# STM32F030P4-DevBoard.net
KiCad netlist of a schematic drawn in Altium Designer
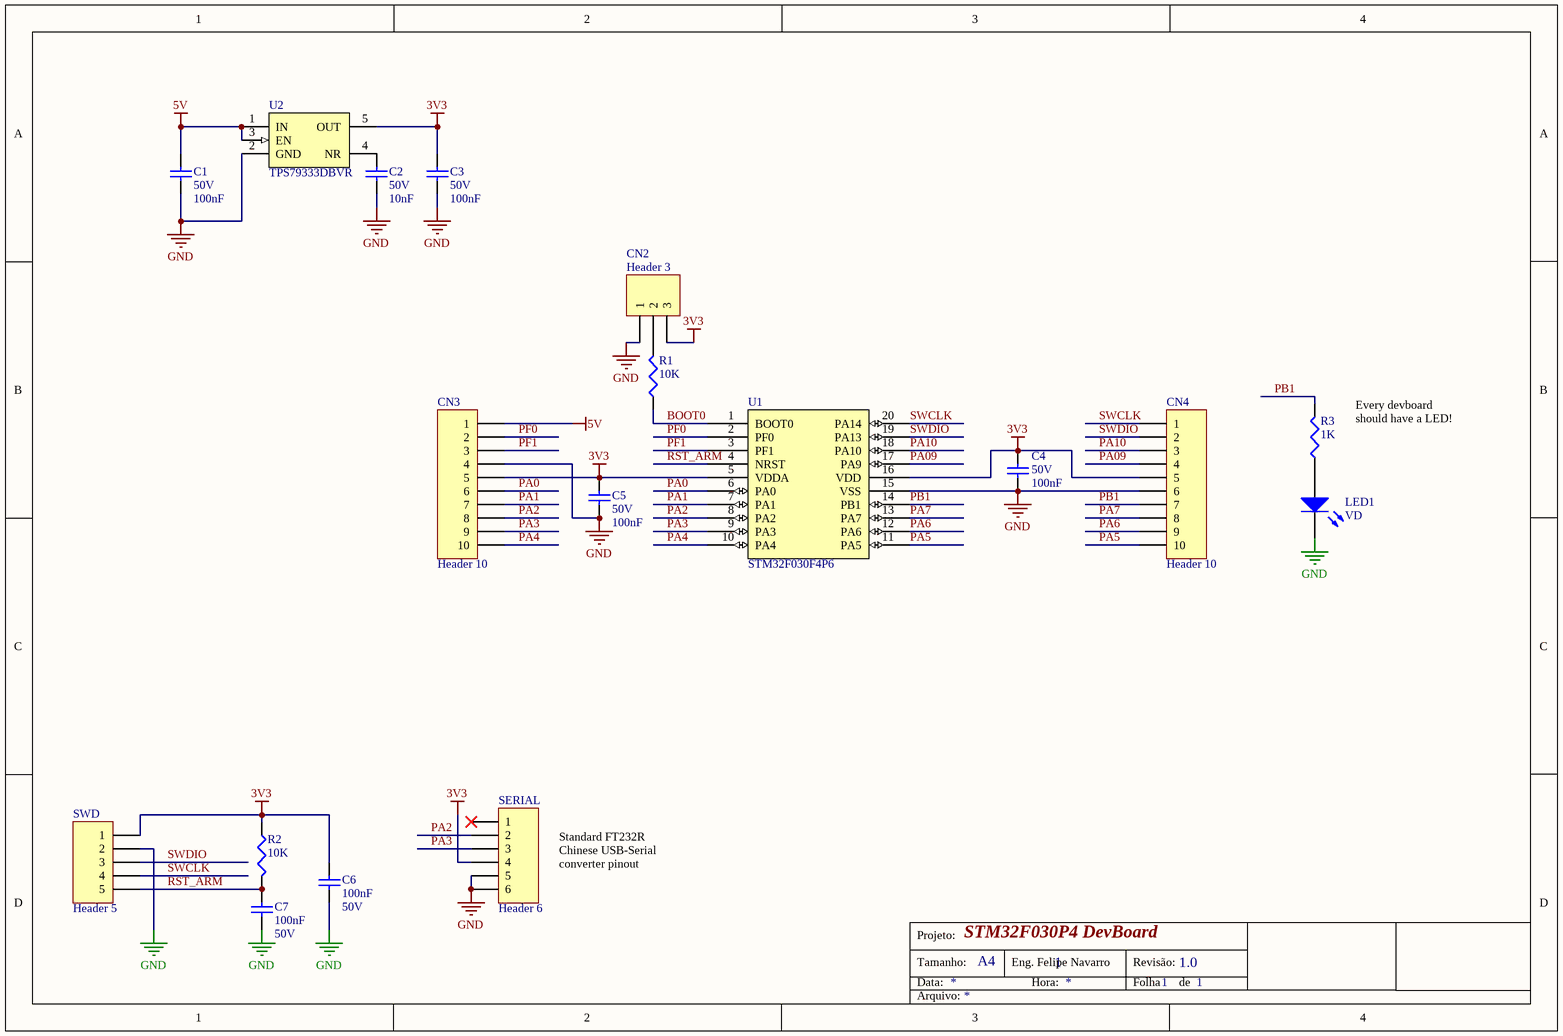
[diagram p0: STM32F030P4-DevBoard.SchDoc]

(export (version "E")
  (design (tool "Eeschema 10.0.6"))
  (components
    (comp (ref "C1")
      (value "100nF")
      (footprint "CC0603")
      (description "Capacitor (Semiconductor SIM Model)")
      (fields (field (name "TENSÃO") "50V") (field (name "Comment") "Capacitor Cerâmico"))
      (libsource (lib "NavarroCAP") (part "Cap 100nF 50V 0603 X7R"))
    )
    (comp (ref "C2")
      (value "10nF")
      (footprint "CC0603")
      (description "Capacitor (Semiconductor SIM Model)")
      (fields (field (name "TENSÃO") "50V") (field (name "Comment") "Capacitor Cerâmico"))
      (libsource (lib "NavarroCAP") (part "Cap 10nF 50V 0603 X7R 5%"))
    )
    (comp (ref "C3")
      (value "100nF")
      (footprint "CC0603")
      (description "Capacitor (Semiconductor SIM Model)")
      (fields (field (name "TENSÃO") "50V") (field (name "Comment") "Capacitor Cerâmico"))
      (libsource (lib "NavarroCAP") (part "Cap 100nF 50V 0603 X7R"))
    )
    (comp (ref "C4")
      (value "100nF")
      (footprint "CC0603")
      (description "Capacitor (Semiconductor SIM Model)")
      (fields (field (name "TENSÃO") "50V") (field (name "Comment") "Capacitor Cerâmico"))
      (libsource (lib "NavarroCAP") (part "Cap 100nF 50V 0603 X7R"))
    )
    (comp (ref "C5")
      (value "100nF")
      (footprint "CC0603")
      (description "Capacitor (Semiconductor SIM Model)")
      (fields (field (name "TENSÃO") "50V") (field (name "Comment") "Capacitor Cerâmico"))
      (libsource (lib "NavarroCAP") (part "Cap 100nF 50V 0603 X7R"))
    )
    (comp (ref "C6")
      (value "100nF")
      (footprint "CC0603")
      (description "Capacitor (Semiconductor SIM Model)")
      (fields (field (name "TENSÃO") "50V") (field (name "Comment") "Capacitor Cerâmico"))
      (libsource (lib "TecnocladeCAP") (part "Cap 100nF 50V 0603 X7R"))
    )
    (comp (ref "C7")
      (value "100nF")
      (footprint "CC0603")
      (description "Capacitor (Semiconductor SIM Model)")
      (fields (field (name "TENSÃO") "50V") (field (name "Comment") "Capacitor Cerâmico"))
      (libsource (lib "TecnocladeCAP") (part "Cap 100nF 50V 0603 X7R"))
    )
    (comp (ref "CN2")
      (value "Header 3")
      (footprint "CONN HDR1X3")
      (description "Header, 3-Pin")
      (libsource (lib "NavarroCON") (part "Header 3"))
    )
    (comp (ref "CN3")
      (value "Header 10")
      (footprint "CONN HDR1X10")
      (description "Header, 10-Pin")
      (libsource (lib "NavarroCON") (part "Header 10"))
    )
    (comp (ref "CN4")
      (value "Header 10")
      (footprint "CONN HDR1X10")
      (description "Header, 10-Pin")
      (libsource (lib "") (part "Header 10_1"))
    )
    (comp (ref "LED1")
      (value "VD")
      (footprint "LED 0603")
      (description "LED")
      (libsource (lib "NavarroSEMI") (part "LED 0603 VD 2V 75mW"))
    )
    (comp (ref "R1")
      (value "10K")
      (footprint "CC0603")
      (description "Resistor")
      (libsource (lib "NavarroRES") (part "Res 10K 1% 0603 1/10W"))
    )
    (comp (ref "R2")
      (value "10K")
      (footprint "CC0603")
      (description "Resistor")
      (libsource (lib "TecnocladeRES") (part "Res 10K 1% 0603 1/10W"))
    )
    (comp (ref "R3")
      (value "1K")
      (footprint "CC0603")
      (description "Resistor")
      (libsource (lib "NavarroRES") (part "Res 1K 1% 0603 1/10W"))
    )
    (comp (ref "SERIAL")
      (value "Header 6")
      (footprint "CONN HDR1X6")
      (description "Header, 6-Pin")
      (libsource (lib "NavarroCON") (part "Header 6"))
    )
    (comp (ref "SWD")
      (value "Header 5")
      (footprint "CONN HDR1X5")
      (description "Header, 5-Pin")
      (libsource (lib "TecnocladeCON") (part "Header 5"))
    )
    (comp (ref "U1")
      (value "STM32F030F4P6")
      (footprint "TSSOP-20N")
      (description "Microcontrolador STM32F030F4P6")
      (libsource (lib "Navarro") (part "STM32F030F4P6"))
    )
    (comp (ref "U2")
      (value "TPS79333DBVR")
      (footprint "SOT-23-5N")
      (description "ULTRALOW-NOISE, HIGH PSRR, FAST RF 200mA LOW-DROPOUT LINEAR  REGULATORS I")
      (libsource (lib "Navarro") (part "TPS79333"))
    )
  )
  (nets
    (net (code "1") (name "/BOOT0") (class "Default")
      (node (ref "R1") (pin "1") (pinfunction "1_1") (pintype "passive"))
      (node (ref "U1") (pin "1") (pinfunction "BOOT0_1") (pintype "passive"))
    )
    (net (code "2") (name "/PA0") (class "Default")
      (node (ref "CN3") (pin "6") (pinfunction "6_6") (pintype "passive"))
      (node (ref "U1") (pin "6") (pinfunction "PA0_6") (pintype "bidirectional"))
    )
    (net (code "3") (name "/PA1") (class "Default")
      (node (ref "CN3") (pin "7") (pinfunction "7_7") (pintype "passive"))
      (node (ref "U1") (pin "7") (pinfunction "PA1_7") (pintype "bidirectional"))
    )
    (net (code "4") (name "/PA2") (class "Default")
      (node (ref "CN3") (pin "8") (pinfunction "8_8") (pintype "passive"))
      (node (ref "SERIAL") (pin "2") (pinfunction "2_2") (pintype "passive"))
      (node (ref "U1") (pin "8") (pinfunction "PA2_8") (pintype "bidirectional"))
    )
    (net (code "5") (name "/PA3") (class "Default")
      (node (ref "CN3") (pin "9") (pinfunction "9_9") (pintype "passive"))
      (node (ref "SERIAL") (pin "3") (pinfunction "3_3") (pintype "passive"))
      (node (ref "U1") (pin "9") (pinfunction "PA3_9") (pintype "bidirectional"))
    )
    (net (code "6") (name "/PA4") (class "Default")
      (node (ref "CN3") (pin "10") (pinfunction "10_10") (pintype "passive"))
      (node (ref "U1") (pin "10") (pinfunction "PA4_10") (pintype "bidirectional"))
    )
    (net (code "7") (name "/PA5") (class "Default")
      (node (ref "CN4") (pin "10") (pinfunction "10_10") (pintype "passive"))
      (node (ref "U1") (pin "11") (pinfunction "PA5_11") (pintype "bidirectional"))
    )
    (net (code "8") (name "/PA6") (class "Default")
      (node (ref "CN4") (pin "9") (pinfunction "9_9") (pintype "passive"))
      (node (ref "U1") (pin "12") (pinfunction "PA6_12") (pintype "bidirectional"))
    )
    (net (code "9") (name "/PA7") (class "Default")
      (node (ref "CN4") (pin "8") (pinfunction "8_8") (pintype "passive"))
      (node (ref "U1") (pin "13") (pinfunction "PA7_13") (pintype "bidirectional"))
    )
    (net (code "10") (name "/PA09") (class "Default")
      (node (ref "CN4") (pin "4") (pinfunction "4_4") (pintype "passive"))
      (node (ref "U1") (pin "17") (pinfunction "PA9_17") (pintype "bidirectional"))
    )
    (net (code "11") (name "/PA10") (class "Default")
      (node (ref "CN4") (pin "3") (pinfunction "3_3") (pintype "passive"))
      (node (ref "U1") (pin "18") (pinfunction "PA10_18") (pintype "bidirectional"))
    )
    (net (code "12") (name "/PB1") (class "Default")
      (node (ref "CN4") (pin "7") (pinfunction "7_7") (pintype "passive"))
      (node (ref "R3") (pin "2") (pinfunction "2_2") (pintype "passive"))
      (node (ref "U1") (pin "14") (pinfunction "PB1_14") (pintype "bidirectional"))
    )
    (net (code "13") (name "/PF0") (class "Default")
      (node (ref "CN3") (pin "2") (pinfunction "2_2") (pintype "passive"))
      (node (ref "U1") (pin "2") (pinfunction "PF0_2") (pintype "passive"))
    )
    (net (code "14") (name "/PF1") (class "Default")
      (node (ref "CN3") (pin "3") (pinfunction "3_3") (pintype "passive"))
      (node (ref "U1") (pin "3") (pinfunction "PF1_3") (pintype "passive"))
    )
    (net (code "15") (name "/RST_ARM") (class "Default")
      (node (ref "C7") (pin "2") (pinfunction "2_2") (pintype "passive"))
      (node (ref "R2") (pin "2") (pinfunction "2_2") (pintype "passive"))
      (node (ref "SWD") (pin "5") (pinfunction "5_5") (pintype "passive"))
      (node (ref "U1") (pin "4") (pinfunction "NRST_4") (pintype "passive"))
    )
    (net (code "16") (name "/SWCLK") (class "Default")
      (node (ref "CN4") (pin "1") (pinfunction "1_1") (pintype "passive"))
      (node (ref "SWD") (pin "4") (pinfunction "4_4") (pintype "passive"))
      (node (ref "U1") (pin "20") (pinfunction "PA14_20") (pintype "bidirectional"))
    )
    (net (code "17") (name "/SWDIO") (class "Default")
      (node (ref "CN4") (pin "2") (pinfunction "2_2") (pintype "passive"))
      (node (ref "SWD") (pin "3") (pinfunction "3_3") (pintype "passive"))
      (node (ref "U1") (pin "19") (pinfunction "PA13_19") (pintype "bidirectional"))
    )
    (net (code "18") (name "3V3") (class "Default")
      (node (ref "C3") (pin "2") (pinfunction "2_2") (pintype "passive"))
      (node (ref "C4") (pin "2") (pinfunction "2_2") (pintype "passive"))
      (node (ref "C5") (pin "2") (pinfunction "2_2") (pintype "passive"))
      (node (ref "C6") (pin "2") (pinfunction "2_2") (pintype "passive"))
      (node (ref "CN2") (pin "3") (pinfunction "3_3") (pintype "passive"))
      (node (ref "CN3") (pin "5") (pinfunction "5_5") (pintype "passive"))
      (node (ref "CN4") (pin "5") (pinfunction "5_5") (pintype "passive"))
      (node (ref "R2") (pin "1") (pinfunction "1_1") (pintype "passive"))
      (node (ref "SERIAL") (pin "4") (pinfunction "4_4") (pintype "passive"))
      (node (ref "SWD") (pin "1") (pinfunction "1_1") (pintype "passive"))
      (node (ref "U1") (pin "16") (pinfunction "VDD_16") (pintype "power_in"))
      (node (ref "U1") (pin "5") (pinfunction "VDDA_5") (pintype "power_in"))
      (node (ref "U2") (pin "5") (pinfunction "OUT_5") (pintype "power_in"))
    )
    (net (code "19") (name "5V") (class "Default")
      (node (ref "C1") (pin "2") (pinfunction "2_2") (pintype "passive"))
      (node (ref "CN3") (pin "1") (pinfunction "1_1") (pintype "passive"))
      (node (ref "U2") (pin "1") (pinfunction "IN_1") (pintype "power_in"))
      (node (ref "U2") (pin "3") (pinfunction "EN_3") (pintype "input"))
    )
    (net (code "20") (name "GND") (class "Default")
      (node (ref "C1") (pin "1") (pinfunction "1_1") (pintype "passive"))
      (node (ref "C2") (pin "1") (pinfunction "1_1") (pintype "passive"))
      (node (ref "C3") (pin "1") (pinfunction "1_1") (pintype "passive"))
      (node (ref "C4") (pin "1") (pinfunction "1_1") (pintype "passive"))
      (node (ref "C5") (pin "1") (pinfunction "1_1") (pintype "passive"))
      (node (ref "C6") (pin "1") (pinfunction "1_1") (pintype "passive"))
      (node (ref "C7") (pin "1") (pinfunction "1_1") (pintype "passive"))
      (node (ref "CN2") (pin "1") (pinfunction "1_1") (pintype "passive"))
      (node (ref "CN3") (pin "4") (pinfunction "4_4") (pintype "passive"))
      (node (ref "CN4") (pin "6") (pinfunction "6_6") (pintype "passive"))
      (node (ref "LED1") (pin "2") (pinfunction "K_2") (pintype "passive"))
      (node (ref "SERIAL") (pin "5") (pinfunction "5_5") (pintype "passive"))
      (node (ref "SERIAL") (pin "6") (pinfunction "6_6") (pintype "passive"))
      (node (ref "SWD") (pin "2") (pinfunction "2_2") (pintype "passive"))
      (node (ref "U1") (pin "15") (pinfunction "VSS_15") (pintype "power_in"))
      (node (ref "U2") (pin "2") (pinfunction "GND_2") (pintype "power_in"))
    )
    (net (code "21") (name "Net-(CN2-Pad2)") (class "Default")
      (node (ref "CN2") (pin "2") (pinfunction "2_2") (pintype "passive"))
      (node (ref "R1") (pin "2") (pinfunction "2_2") (pintype "passive"))
    )
    (net (code "22") (name "Net-(LED1-A)") (class "Default")
      (node (ref "LED1") (pin "1") (pinfunction "A_1") (pintype "passive"))
      (node (ref "R3") (pin "1") (pinfunction "1_1") (pintype "passive"))
    )
    (net (code "23") (name "Net-(U2-NR)") (class "Default")
      (node (ref "C2") (pin "2") (pinfunction "2_2") (pintype "passive"))
      (node (ref "U2") (pin "4") (pinfunction "NR_4") (pintype "passive"))
    )
    (net (code "24") (name "unconnected-(SERIAL-Pad1)") (class "Default")
      (node (ref "SERIAL") (pin "1") (pinfunction "1_1") (pintype "passive+no_connect"))
    )
  )
)
